# EasyEdaSchematic.net
KiCad netlist of a schematic drawn in EasyEDA
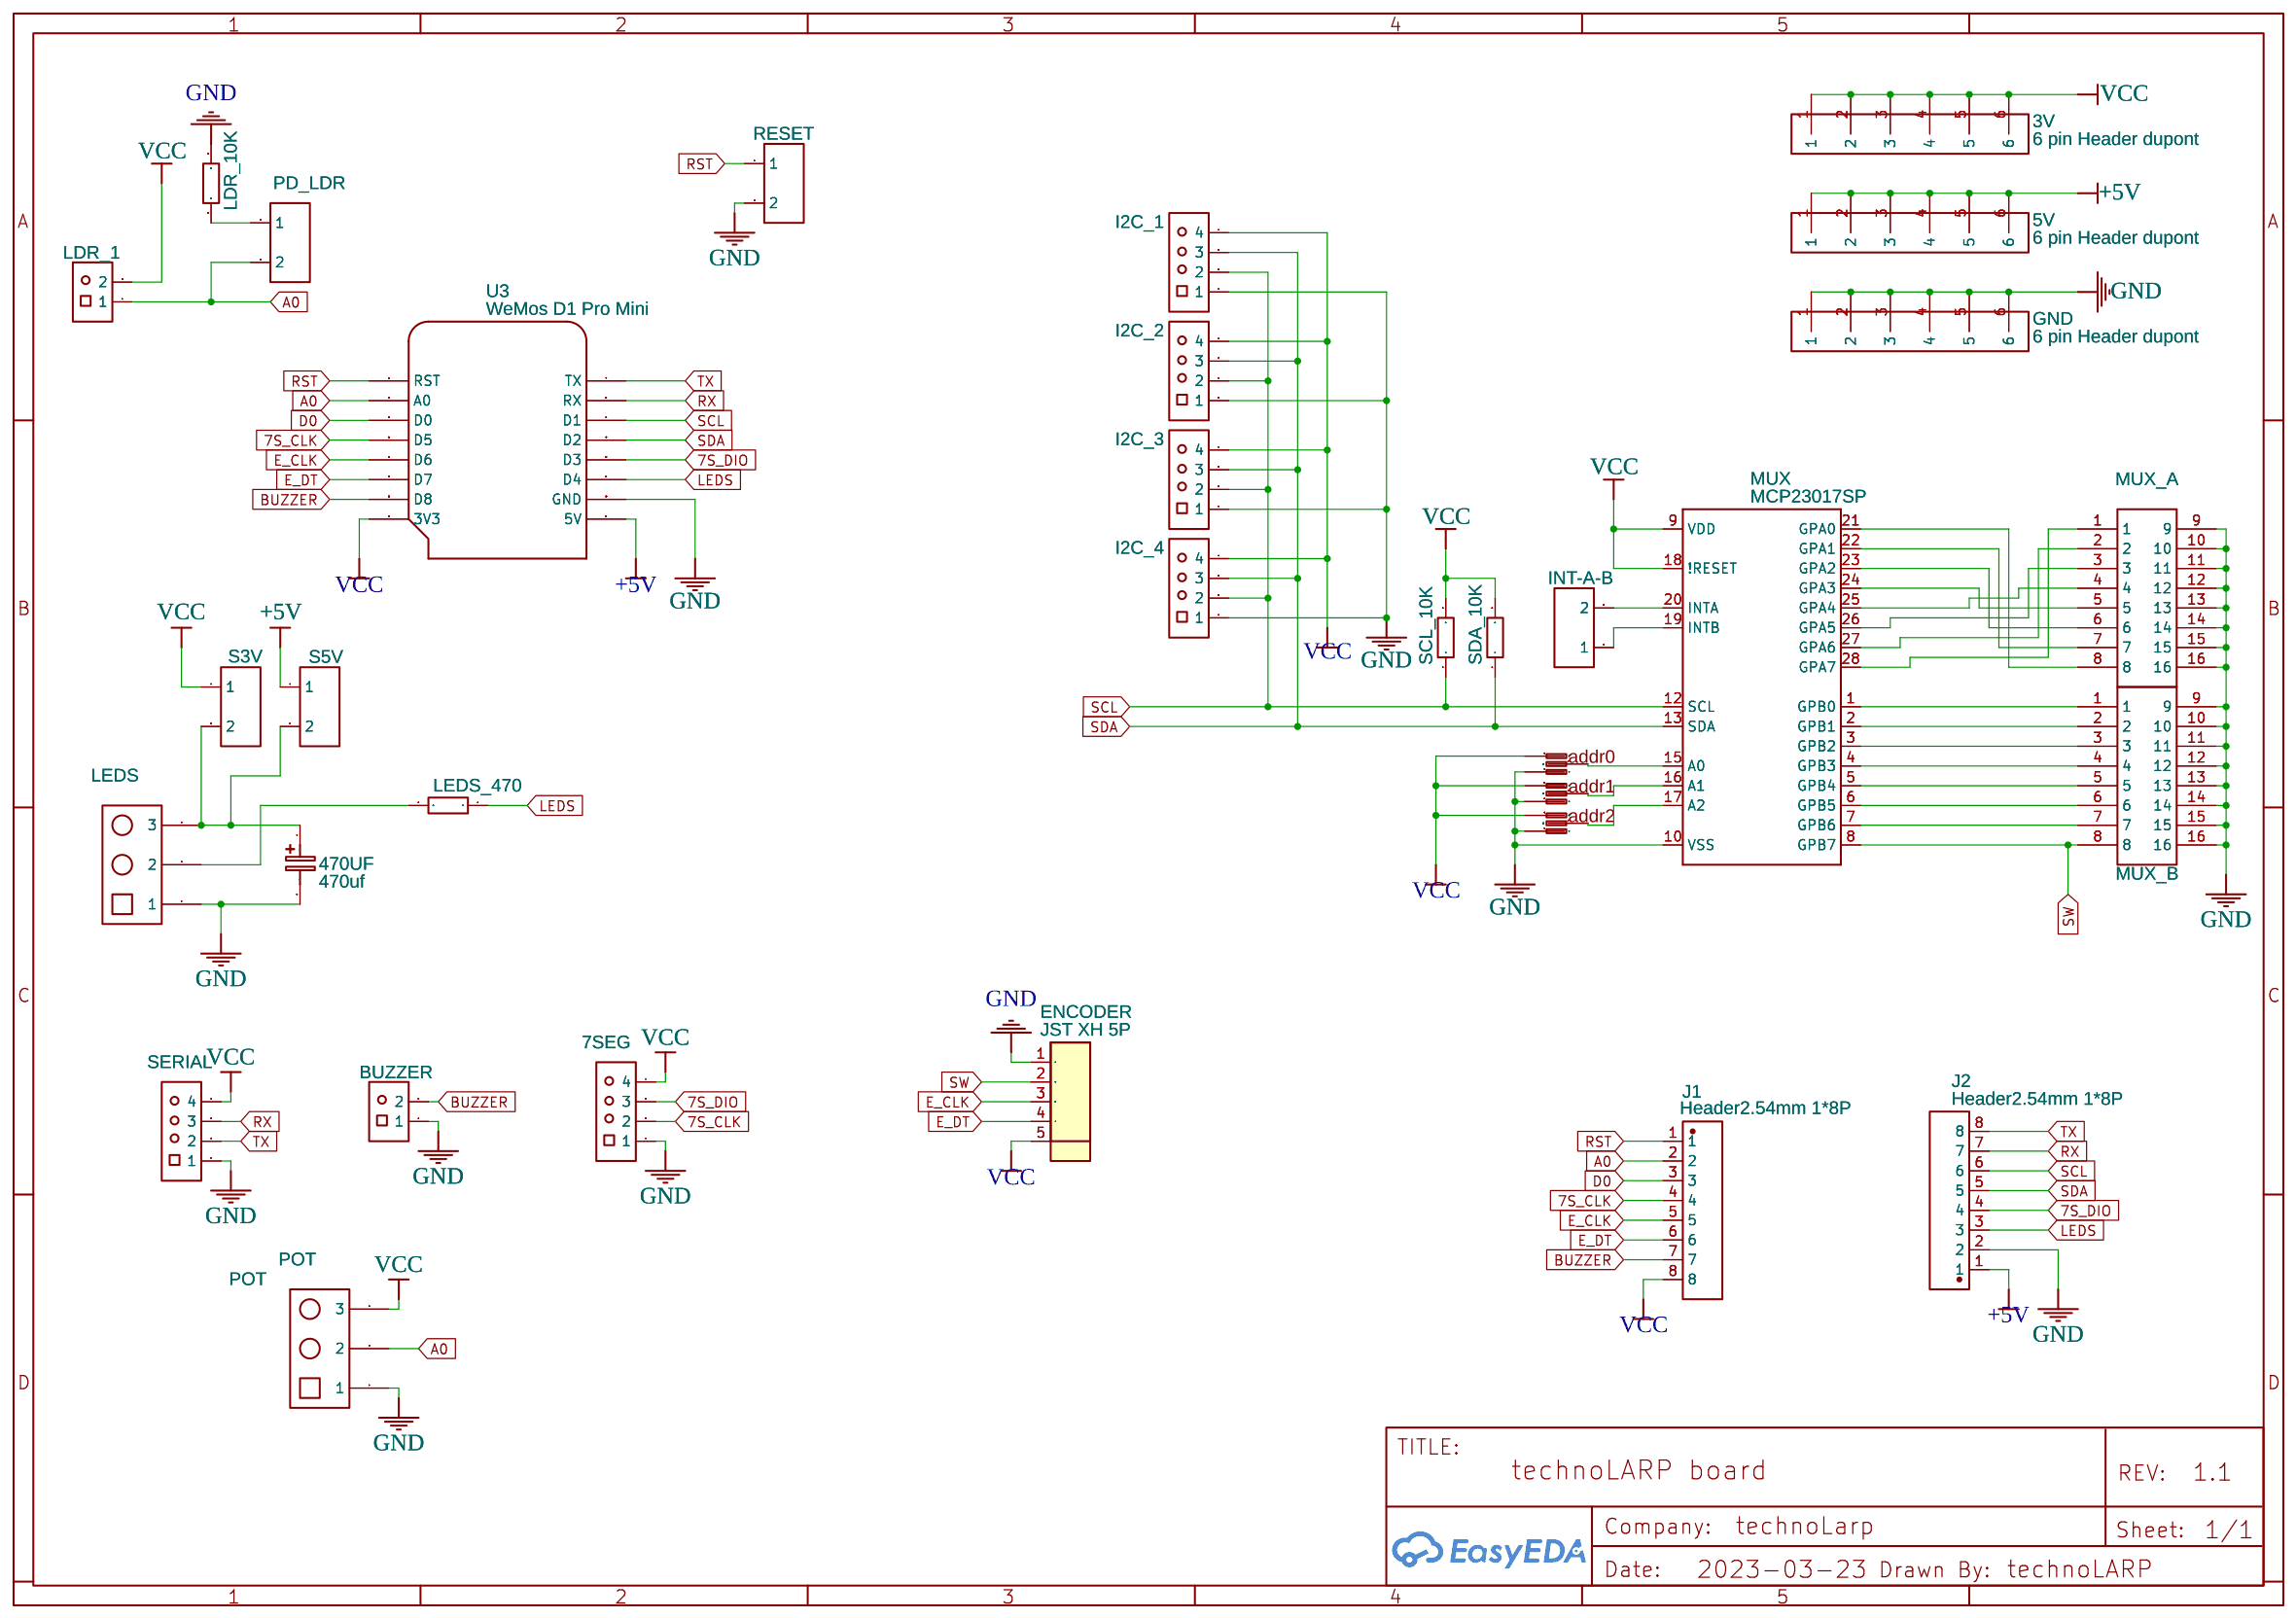
[diagram p0: schematic sheet]

(export (version "E")
  (design (tool "Eeschema 10.0.6"))
  (components
    (comp (ref "3V") (value "6 pin Header dupont") (libsource (lib "") (part "6 pin Header dupont_2")))
    (comp (ref "5V") (value "6 pin Header dupont") (libsource (lib "") (part "6 pin Header dupont")))
    (comp (ref "7SEG")
      (value "7SEG")
      (fields (field (name "Manufacturer Part") "JST_XH CONNECTOR"))
      (libsource (lib "") (part "Unknown_315_-275"))
    )
    (comp (ref "470UF") (value "470uf") (libsource (lib "") (part "Cap_Electrolytic(TH)_D5.0XF2.0_EU")))
    (comp (ref "ADDR0") (value "3 PAD SOLDER JUMPER") (libsource (lib "") (part "3 PAD SOLDER JUMPER_1")))
    (comp (ref "ADDR1") (value "3 PAD SOLDER JUMPER") (libsource (lib "") (part "3 PAD SOLDER JUMPER_2")))
    (comp (ref "ADDR2") (value "3 PAD SOLDER JUMPER") (libsource (lib "") (part "3 PAD SOLDER JUMPER")))
    (comp (ref "BUZZER")
      (value "BUZZER")
      (fields (field (name "Manufacturer Part") "JST_XH CONNECTOR"))
      (libsource (lib "") (part "Unknown_200_-265"))
    )
    (comp (ref "ENCODER") (value "JST XH 5P") (libsource (lib "") (part "JST XH 5P")))
    (comp (ref "GND") (value "6 pin Header dupont") (libsource (lib "") (part "6 pin Header dupont_1")))
    (comp (ref "I2C_1")
      (value "I2C_1")
      (fields (field (name "Manufacturer Part") "JST_XH CONNECTOR"))
      (libsource (lib "") (part "Unknown_605_-705"))
    )
    (comp (ref "I2C_2")
      (value "I2C_2")
      (fields (field (name "Manufacturer Part") "JST_XH CONNECTOR"))
      (libsource (lib "") (part "Unknown_605_-650"))
    )
    (comp (ref "I2C_3")
      (value "I2C_3")
      (fields (field (name "Manufacturer Part") "JST_XH CONNECTOR"))
      (libsource (lib "") (part "Unknown_605_-595"))
    )
    (comp (ref "I2C_4")
      (value "I2C_4")
      (fields (field (name "Manufacturer Part") "JST_XH CONNECTOR"))
      (libsource (lib "") (part "Unknown_605_-540"))
    )
    (comp (ref "INT-A-B")
      (value "Header-Male-2.54_1x2")
      (fields (field (name "Manufacturer Part") "826629-2") (field (name "Manufacturer") "TE Connectivity"))
      (libsource (lib "") (part "Header-Male-2.54_1x2_4"))
    )
    (comp (ref "J1")
      (value "Header2.54mm 1*8P")
      (fields (field (name "Manufacturer") "ReliaPro"))
      (libsource (lib "") (part "Header2.54mm 1*8P_1"))
    )
    (comp (ref "J2")
      (value "Header2.54mm 1*8P")
      (fields (field (name "Manufacturer") "ReliaPro"))
      (libsource (lib "") (part "Header2.54mm 1*8P"))
    )
    (comp (ref "LDR")
      (value "LDR_1")
      (fields (field (name "Manufacturer Part") "JST_XH CONNECTOR"))
      (libsource (lib "") (part "Unknown_50_-680"))
    )
    (comp (ref "LDR_10K")
      (value "10k")
      (fields (field (name "Manufacturer Part") "?"))
      (libsource (lib "") (part "Res_AXIAL-0.3(1/8W)_EU_3"))
    )
    (comp (ref "LEDS") (value "JST-XH-03P") (libsource (lib "") (part "JST-XH-03P")))
    (comp (ref "LEDS_470")
      (value "10k")
      (fields (field (name "Manufacturer Part") "?"))
      (libsource (lib "") (part "Res_AXIAL-0.3(1/8W)_EU_1"))
    )
    (comp (ref "MUX")
      (value "MCP23017SP")
      (fields (field (name "Manufacturer Part") "?"))
      (libsource (lib "") (part "Unknown_885_-465"))
    )
    (comp (ref "MUX_A") (value "2x8pin") (libsource (lib "") (part "2x8pin_1")))
    (comp (ref "MUX_B") (value "2x8pin") (libsource (lib "") (part "2x8pin")))
    (comp (ref "PD_LDR")
      (value "Header-Male-2.54_1x2")
      (fields (field (name "Manufacturer Part") "826629-2") (field (name "Manufacturer") "TE Connectivity"))
      (libsource (lib "") (part "Header-Male-2.54_1x2"))
    )
    (comp (ref "POT") (value "POT") (libsource (lib "") (part "JST-XH-03P_1")))
    (comp (ref "RESET")
      (value "RESET")
      (fields (field (name "Manufacturer Part") "826629-2") (field (name "Manufacturer") "TE Connectivity"))
      (libsource (lib "") (part "Header-Male-2.54_1x2_1"))
    )
    (comp (ref "RXTX")
      (value "SERIAL")
      (fields (field (name "Manufacturer Part") "JST_XH CONNECTOR"))
      (libsource (lib "") (part "Unknown_95_-265"))
    )
    (comp (ref "S3V")
      (value "RESET")
      (fields (field (name "Manufacturer Part") "826629-2") (field (name "Manufacturer") "TE Connectivity"))
      (libsource (lib "") (part "Header-Male-2.54_1x2_3"))
    )
    (comp (ref "S5V")
      (value "RESET")
      (fields (field (name "Manufacturer Part") "826629-2") (field (name "Manufacturer") "TE Connectivity"))
      (libsource (lib "") (part "Header-Male-2.54_1x2_2"))
    )
    (comp (ref "SCL_10K")
      (value "10k")
      (fields (field (name "Manufacturer Part") "?"))
      (libsource (lib "") (part "Res_AXIAL-0.3(1/8W)_EU_2"))
    )
    (comp (ref "SDA_10K")
      (value "10k")
      (fields (field (name "Manufacturer Part") "?"))
      (libsource (lib "") (part "Res_AXIAL-0.3(1/8W)_EU"))
    )
    (comp (ref "U3")
      (value "WeMos D1 Pro Mini")
      (fields (field (name "Manufacturer Part") "WeMos D1 Mini Pro"))
      (libsource (lib "") (part "WeMos D1 Pro Mini"))
    )
  )
  (nets
    (net (code "1") (name "+5V") (class "Default")
      (node (ref "5V") (pin "1") (pinfunction "1_1") (pintype "unspecified"))
      (node (ref "5V") (pin "2") (pinfunction "2_2") (pintype "unspecified"))
      (node (ref "5V") (pin "3") (pinfunction "3_3") (pintype "unspecified"))
      (node (ref "5V") (pin "4") (pinfunction "4_4") (pintype "unspecified"))
      (node (ref "5V") (pin "5") (pinfunction "5_5") (pintype "unspecified"))
      (node (ref "5V") (pin "6") (pinfunction "6_6") (pintype "unspecified"))
      (node (ref "J2") (pin "1") (pinfunction "1_1") (pintype "unspecified"))
      (node (ref "S5V") (pin "1") (pinfunction "1_1") (pintype "unspecified"))
      (node (ref "U3") (pin "5V") (pinfunction "5V_5V") (pintype "unspecified"))
    )
    (net (code "2") (name "7S_CLK") (class "Default")
      (node (ref "7SEG") (pin "2") (pinfunction "2_2") (pintype "unspecified"))
      (node (ref "J1") (pin "4") (pinfunction "4_4") (pintype "unspecified"))
      (node (ref "U3") (pin "D5") (pinfunction "D5_D5") (pintype "unspecified"))
    )
    (net (code "3") (name "7S_DIO") (class "Default")
      (node (ref "7SEG") (pin "3") (pinfunction "3_3") (pintype "unspecified"))
      (node (ref "J2") (pin "4") (pinfunction "4_4") (pintype "unspecified"))
      (node (ref "U3") (pin "D3") (pinfunction "D3_D3") (pintype "unspecified"))
    )
    (net (code "4") (name "A0") (class "Default")
      (node (ref "J1") (pin "2") (pinfunction "2_2") (pintype "unspecified"))
      (node (ref "LDR") (pin "1") (pinfunction "1_1") (pintype "unspecified"))
      (node (ref "PD_LDR") (pin "2") (pinfunction "2_2") (pintype "unspecified"))
      (node (ref "POT") (pin "2") (pinfunction "2_2") (pintype "unspecified"))
      (node (ref "U3") (pin "A0") (pinfunction "A0_A0") (pintype "unspecified"))
    )
    (net (code "5") (name "BUZZER") (class "Default")
      (node (ref "BUZZER") (pin "2") (pinfunction "2_2") (pintype "unspecified"))
      (node (ref "J1") (pin "7") (pinfunction "7_7") (pintype "unspecified"))
      (node (ref "U3") (pin "D8") (pinfunction "D8_D8") (pintype "unspecified"))
    )
    (net (code "6") (name "D0") (class "Default")
      (node (ref "J1") (pin "3") (pinfunction "3_3") (pintype "unspecified"))
      (node (ref "U3") (pin "D0") (pinfunction "D0_D0") (pintype "unspecified"))
    )
    (net (code "7") (name "E_CLK") (class "Default")
      (node (ref "ENCODER") (pin "3") (pinfunction "3_3") (pintype "unspecified"))
      (node (ref "J1") (pin "5") (pinfunction "5_5") (pintype "unspecified"))
      (node (ref "U3") (pin "D6") (pinfunction "D6_D6") (pintype "unspecified"))
    )
    (net (code "8") (name "E_DT") (class "Default")
      (node (ref "ENCODER") (pin "4") (pinfunction "4_4") (pintype "unspecified"))
      (node (ref "J1") (pin "6") (pinfunction "6_6") (pintype "unspecified"))
      (node (ref "U3") (pin "D7") (pinfunction "D7_D7") (pintype "unspecified"))
    )
    (net (code "9") (name "GND") (class "Default")
      (node (ref "470UF") (pin "2") (pinfunction "2_2") (pintype "unspecified"))
      (node (ref "7SEG") (pin "1") (pinfunction "1_1") (pintype "unspecified"))
      (node (ref "ADDR0") (pin "1") (pinfunction "1_1") (pintype "unspecified"))
      (node (ref "ADDR1") (pin "1") (pinfunction "1_1") (pintype "unspecified"))
      (node (ref "ADDR2") (pin "1") (pinfunction "1_1") (pintype "unspecified"))
      (node (ref "BUZZER") (pin "1") (pinfunction "1_1") (pintype "unspecified"))
      (node (ref "ENCODER") (pin "1") (pinfunction "1_1") (pintype "unspecified"))
      (node (ref "GND") (pin "1") (pinfunction "1_1") (pintype "unspecified"))
      (node (ref "GND") (pin "2") (pinfunction "2_2") (pintype "unspecified"))
      (node (ref "GND") (pin "3") (pinfunction "3_3") (pintype "unspecified"))
      (node (ref "GND") (pin "4") (pinfunction "4_4") (pintype "unspecified"))
      (node (ref "GND") (pin "5") (pinfunction "5_5") (pintype "unspecified"))
      (node (ref "GND") (pin "6") (pinfunction "6_6") (pintype "unspecified"))
      (node (ref "I2C_1") (pin "1") (pinfunction "1_1") (pintype "unspecified"))
      (node (ref "I2C_2") (pin "1") (pinfunction "1_1") (pintype "unspecified"))
      (node (ref "I2C_3") (pin "1") (pinfunction "1_1") (pintype "unspecified"))
      (node (ref "I2C_4") (pin "1") (pinfunction "1_1") (pintype "unspecified"))
      (node (ref "J2") (pin "2") (pinfunction "2_2") (pintype "unspecified"))
      (node (ref "LDR_10K") (pin "2") (pinfunction "2_2") (pintype "unspecified"))
      (node (ref "LEDS") (pin "1") (pinfunction "1_1") (pintype "unspecified"))
      (node (ref "MUX") (pin "10") (pinfunction "VSS_10") (pintype "passive"))
      (node (ref "MUX_A") (pin "10") (pinfunction "10_10") (pintype "unspecified"))
      (node (ref "MUX_A") (pin "11") (pinfunction "11_11") (pintype "unspecified"))
      (node (ref "MUX_A") (pin "12") (pinfunction "12_12") (pintype "unspecified"))
      (node (ref "MUX_A") (pin "13") (pinfunction "13_13") (pintype "unspecified"))
      (node (ref "MUX_A") (pin "14") (pinfunction "14_14") (pintype "unspecified"))
      (node (ref "MUX_A") (pin "15") (pinfunction "15_15") (pintype "unspecified"))
      (node (ref "MUX_A") (pin "16") (pinfunction "16_16") (pintype "unspecified"))
      (node (ref "MUX_A") (pin "9") (pinfunction "9_9") (pintype "unspecified"))
      (node (ref "MUX_B") (pin "10") (pinfunction "10_10") (pintype "unspecified"))
      (node (ref "MUX_B") (pin "11") (pinfunction "11_11") (pintype "unspecified"))
      (node (ref "MUX_B") (pin "12") (pinfunction "12_12") (pintype "unspecified"))
      (node (ref "MUX_B") (pin "13") (pinfunction "13_13") (pintype "unspecified"))
      (node (ref "MUX_B") (pin "14") (pinfunction "14_14") (pintype "unspecified"))
      (node (ref "MUX_B") (pin "15") (pinfunction "15_15") (pintype "unspecified"))
      (node (ref "MUX_B") (pin "16") (pinfunction "16_16") (pintype "unspecified"))
      (node (ref "MUX_B") (pin "9") (pinfunction "9_9") (pintype "unspecified"))
      (node (ref "POT") (pin "1") (pinfunction "1_1") (pintype "unspecified"))
      (node (ref "RESET") (pin "2") (pinfunction "2_2") (pintype "unspecified"))
      (node (ref "RXTX") (pin "1") (pinfunction "1_1") (pintype "unspecified"))
      (node (ref "U3") (pin "GND") (pinfunction "GND_GND") (pintype "unspecified"))
    )
    (net (code "10") (name "LEDS") (class "Default")
      (node (ref "J2") (pin "3") (pinfunction "3_3") (pintype "unspecified"))
      (node (ref "LEDS_470") (pin "1") (pinfunction "1_1") (pintype "unspecified"))
      (node (ref "U3") (pin "D4") (pinfunction "D4_D4") (pintype "unspecified"))
    )
    (net (code "11") (name "Net-(470UF-Pad1)") (class "Default")
      (node (ref "470UF") (pin "1") (pinfunction "1_1") (pintype "unspecified"))
      (node (ref "LEDS") (pin "3") (pinfunction "3_3") (pintype "unspecified"))
      (node (ref "S3V") (pin "2") (pinfunction "2_2") (pintype "unspecified"))
      (node (ref "S5V") (pin "2") (pinfunction "2_2") (pintype "unspecified"))
    )
    (net (code "12") (name "Net-(ADDR0-BOOT)") (class "Default")
      (node (ref "ADDR0") (pin "2") (pinfunction "BOOT_2") (pintype "unspecified"))
      (node (ref "MUX") (pin "15") (pinfunction "A0_15") (pintype "input"))
    )
    (net (code "13") (name "Net-(ADDR1-BOOT)") (class "Default")
      (node (ref "ADDR1") (pin "2") (pinfunction "BOOT_2") (pintype "unspecified"))
      (node (ref "MUX") (pin "16") (pinfunction "A1_16") (pintype "input"))
    )
    (net (code "14") (name "Net-(ADDR2-BOOT)") (class "Default")
      (node (ref "ADDR2") (pin "2") (pinfunction "BOOT_2") (pintype "unspecified"))
      (node (ref "MUX") (pin "17") (pinfunction "A2_17") (pintype "input"))
    )
    (net (code "15") (name "Net-(LDR_10K-Pad1)") (class "Default")
      (node (ref "LDR_10K") (pin "1") (pinfunction "1_1") (pintype "unspecified"))
      (node (ref "PD_LDR") (pin "1") (pinfunction "1_1") (pintype "unspecified"))
    )
    (net (code "16") (name "Net-(LEDS-Pad2)") (class "Default")
      (node (ref "LEDS") (pin "2") (pinfunction "2_2") (pintype "unspecified"))
      (node (ref "LEDS_470") (pin "2") (pinfunction "2_2") (pintype "unspecified"))
    )
    (net (code "17") (name "Net-(MUX-GPA0)") (class "Default")
      (node (ref "MUX") (pin "21") (pinfunction "GPA0_21") (pintype "unspecified"))
      (node (ref "MUX_A") (pin "8") (pinfunction "8_8") (pintype "unspecified"))
    )
    (net (code "18") (name "Net-(MUX-GPA1)") (class "Default")
      (node (ref "MUX") (pin "22") (pinfunction "GPA1_22") (pintype "unspecified"))
      (node (ref "MUX_A") (pin "7") (pinfunction "7_7") (pintype "unspecified"))
    )
    (net (code "19") (name "Net-(MUX-GPA2)") (class "Default")
      (node (ref "MUX") (pin "23") (pinfunction "GPA2_23") (pintype "unspecified"))
      (node (ref "MUX_A") (pin "6") (pinfunction "6_6") (pintype "unspecified"))
    )
    (net (code "20") (name "Net-(MUX-GPA3)") (class "Default")
      (node (ref "MUX") (pin "24") (pinfunction "GPA3_24") (pintype "unspecified"))
      (node (ref "MUX_A") (pin "5") (pinfunction "5_5") (pintype "unspecified"))
    )
    (net (code "21") (name "Net-(MUX-GPA4)") (class "Default")
      (node (ref "MUX") (pin "25") (pinfunction "GPA4_25") (pintype "unspecified"))
      (node (ref "MUX_A") (pin "4") (pinfunction "4_4") (pintype "unspecified"))
    )
    (net (code "22") (name "Net-(MUX-GPA5)") (class "Default")
      (node (ref "MUX") (pin "26") (pinfunction "GPA5_26") (pintype "unspecified"))
      (node (ref "MUX_A") (pin "3") (pinfunction "3_3") (pintype "unspecified"))
    )
    (net (code "23") (name "Net-(MUX-GPA6)") (class "Default")
      (node (ref "MUX") (pin "27") (pinfunction "GPA6_27") (pintype "unspecified"))
      (node (ref "MUX_A") (pin "2") (pinfunction "2_2") (pintype "unspecified"))
    )
    (net (code "24") (name "Net-(MUX-GPA7)") (class "Default")
      (node (ref "MUX") (pin "28") (pinfunction "GPA7_28") (pintype "unspecified"))
      (node (ref "MUX_A") (pin "1") (pinfunction "1_1") (pintype "unspecified"))
    )
    (net (code "25") (name "Net-(MUX-GPB0)") (class "Default")
      (node (ref "MUX") (pin "1") (pinfunction "GPB0_1") (pintype "unspecified"))
      (node (ref "MUX_B") (pin "1") (pinfunction "1_1") (pintype "unspecified"))
    )
    (net (code "26") (name "Net-(MUX-GPB1)") (class "Default")
      (node (ref "MUX") (pin "2") (pinfunction "GPB1_2") (pintype "unspecified"))
      (node (ref "MUX_B") (pin "2") (pinfunction "2_2") (pintype "unspecified"))
    )
    (net (code "27") (name "Net-(MUX-GPB2)") (class "Default")
      (node (ref "MUX") (pin "3") (pinfunction "GPB2_3") (pintype "unspecified"))
      (node (ref "MUX_B") (pin "3") (pinfunction "3_3") (pintype "unspecified"))
    )
    (net (code "28") (name "Net-(MUX-GPB3)") (class "Default")
      (node (ref "MUX") (pin "4") (pinfunction "GPB3_4") (pintype "unspecified"))
      (node (ref "MUX_B") (pin "4") (pinfunction "4_4") (pintype "unspecified"))
    )
    (net (code "29") (name "Net-(MUX-GPB4)") (class "Default")
      (node (ref "MUX") (pin "5") (pinfunction "GPB4_5") (pintype "unspecified"))
      (node (ref "MUX_B") (pin "5") (pinfunction "5_5") (pintype "unspecified"))
    )
    (net (code "30") (name "Net-(MUX-GPB5)") (class "Default")
      (node (ref "MUX") (pin "6") (pinfunction "GPB5_6") (pintype "unspecified"))
      (node (ref "MUX_B") (pin "6") (pinfunction "6_6") (pintype "unspecified"))
    )
    (net (code "31") (name "Net-(MUX-GPB6)") (class "Default")
      (node (ref "MUX") (pin "7") (pinfunction "GPB6_7") (pintype "unspecified"))
      (node (ref "MUX_B") (pin "7") (pinfunction "7_7") (pintype "unspecified"))
    )
    (net (code "32") (name "Net-(MUX-INTA)") (class "Default")
      (node (ref "INT-A-B") (pin "2") (pinfunction "2_2") (pintype "unspecified"))
      (node (ref "MUX") (pin "20") (pinfunction "INTA_20") (pintype "output"))
    )
    (net (code "33") (name "Net-(MUX-INTB)") (class "Default")
      (node (ref "INT-A-B") (pin "1") (pinfunction "1_1") (pintype "unspecified"))
      (node (ref "MUX") (pin "19") (pinfunction "INTB_19") (pintype "output"))
    )
    (net (code "34") (name "RST") (class "Default")
      (node (ref "J1") (pin "1") (pinfunction "1_1") (pintype "unspecified"))
      (node (ref "RESET") (pin "1") (pinfunction "1_1") (pintype "unspecified"))
      (node (ref "U3") (pin "RST") (pinfunction "RST_RST") (pintype "unspecified"))
    )
    (net (code "35") (name "RX") (class "Default")
      (node (ref "J2") (pin "7") (pinfunction "7_7") (pintype "unspecified"))
      (node (ref "RXTX") (pin "3") (pinfunction "3_3") (pintype "unspecified"))
      (node (ref "U3") (pin "RX") (pinfunction "RX_RX") (pintype "unspecified"))
    )
    (net (code "36") (name "SCL") (class "Default")
      (node (ref "I2C_1") (pin "2") (pinfunction "2_2") (pintype "unspecified"))
      (node (ref "I2C_2") (pin "2") (pinfunction "2_2") (pintype "unspecified"))
      (node (ref "I2C_3") (pin "2") (pinfunction "2_2") (pintype "unspecified"))
      (node (ref "I2C_4") (pin "2") (pinfunction "2_2") (pintype "unspecified"))
      (node (ref "J2") (pin "6") (pinfunction "6_6") (pintype "unspecified"))
      (node (ref "MUX") (pin "12") (pinfunction "SCL_12") (pintype "input"))
      (node (ref "SCL_10K") (pin "1") (pinfunction "1_1") (pintype "unspecified"))
      (node (ref "U3") (pin "D1") (pinfunction "D1_D1") (pintype "unspecified"))
    )
    (net (code "37") (name "SDA") (class "Default")
      (node (ref "I2C_1") (pin "3") (pinfunction "3_3") (pintype "unspecified"))
      (node (ref "I2C_2") (pin "3") (pinfunction "3_3") (pintype "unspecified"))
      (node (ref "I2C_3") (pin "3") (pinfunction "3_3") (pintype "unspecified"))
      (node (ref "I2C_4") (pin "3") (pinfunction "3_3") (pintype "unspecified"))
      (node (ref "J2") (pin "5") (pinfunction "5_5") (pintype "unspecified"))
      (node (ref "MUX") (pin "13") (pinfunction "SDA_13") (pintype "unspecified"))
      (node (ref "SDA_10K") (pin "1") (pinfunction "1_1") (pintype "unspecified"))
      (node (ref "U3") (pin "D2") (pinfunction "D2_D2") (pintype "unspecified"))
    )
    (net (code "38") (name "SW") (class "Default")
      (node (ref "ENCODER") (pin "2") (pinfunction "2_2") (pintype "unspecified"))
      (node (ref "MUX") (pin "8") (pinfunction "GPB7_8") (pintype "unspecified"))
      (node (ref "MUX_B") (pin "8") (pinfunction "8_8") (pintype "unspecified"))
    )
    (net (code "39") (name "TX") (class "Default")
      (node (ref "J2") (pin "8") (pinfunction "8_8") (pintype "unspecified"))
      (node (ref "RXTX") (pin "2") (pinfunction "2_2") (pintype "unspecified"))
      (node (ref "U3") (pin "TX") (pinfunction "TX_TX") (pintype "unspecified"))
    )
    (net (code "40") (name "VCC") (class "Default")
      (node (ref "3V") (pin "1") (pinfunction "1_1") (pintype "unspecified"))
      (node (ref "3V") (pin "2") (pinfunction "2_2") (pintype "unspecified"))
      (node (ref "3V") (pin "3") (pinfunction "3_3") (pintype "unspecified"))
      (node (ref "3V") (pin "4") (pinfunction "4_4") (pintype "unspecified"))
      (node (ref "3V") (pin "5") (pinfunction "5_5") (pintype "unspecified"))
      (node (ref "3V") (pin "6") (pinfunction "6_6") (pintype "unspecified"))
      (node (ref "7SEG") (pin "4") (pinfunction "4_4") (pintype "unspecified"))
      (node (ref "ADDR0") (pin "3") (pinfunction "0_3") (pintype "unspecified"))
      (node (ref "ADDR1") (pin "3") (pinfunction "0_3") (pintype "unspecified"))
      (node (ref "ADDR2") (pin "3") (pinfunction "0_3") (pintype "unspecified"))
      (node (ref "ENCODER") (pin "5") (pinfunction "5_5") (pintype "unspecified"))
      (node (ref "I2C_1") (pin "4") (pinfunction "4_4") (pintype "unspecified"))
      (node (ref "I2C_2") (pin "4") (pinfunction "4_4") (pintype "unspecified"))
      (node (ref "I2C_3") (pin "4") (pinfunction "4_4") (pintype "unspecified"))
      (node (ref "I2C_4") (pin "4") (pinfunction "4_4") (pintype "unspecified"))
      (node (ref "J1") (pin "8") (pinfunction "8_8") (pintype "unspecified"))
      (node (ref "LDR") (pin "2") (pinfunction "2_2") (pintype "unspecified"))
      (node (ref "MUX") (pin "18") (pinfunction "!RESET_18") (pintype "input"))
      (node (ref "MUX") (pin "9") (pinfunction "VDD_9") (pintype "passive"))
      (node (ref "POT") (pin "3") (pinfunction "3_3") (pintype "unspecified"))
      (node (ref "RXTX") (pin "4") (pinfunction "4_4") (pintype "unspecified"))
      (node (ref "S3V") (pin "1") (pinfunction "1_1") (pintype "unspecified"))
      (node (ref "SCL_10K") (pin "2") (pinfunction "2_2") (pintype "unspecified"))
      (node (ref "SDA_10K") (pin "2") (pinfunction "2_2") (pintype "unspecified"))
      (node (ref "U3") (pin "3V3") (pinfunction "3V3_3V3") (pintype "unspecified"))
    )
  )
)
